# PI2AX.net
KiCad netlist of a schematic drawn in EAGLE
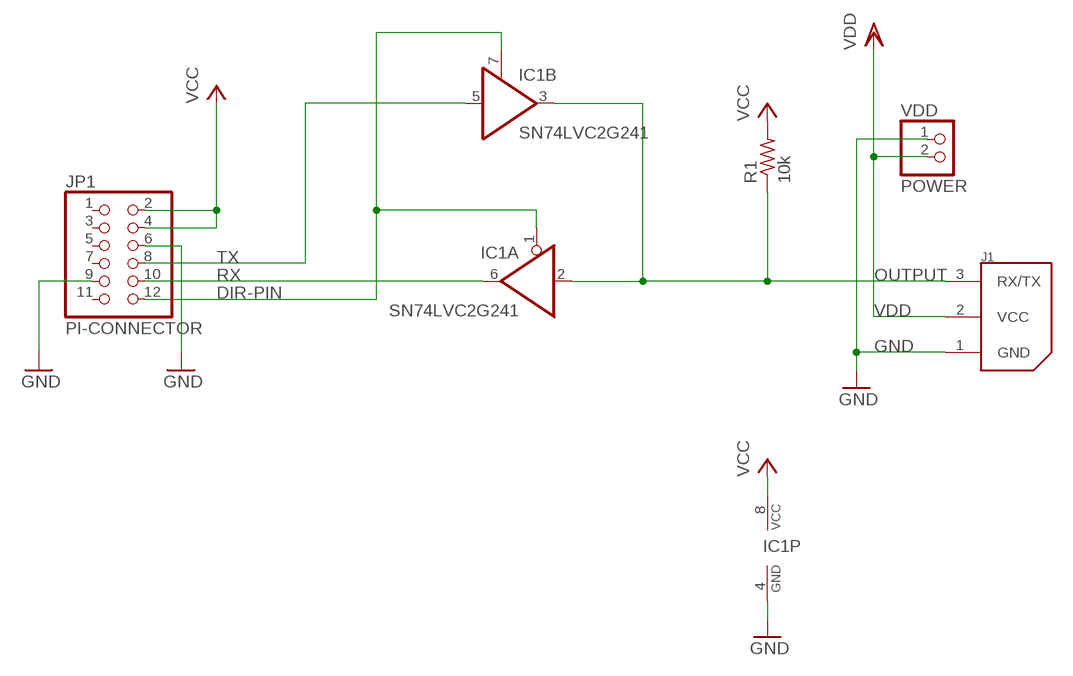
[diagram p0: schematic, sheet 1]

(export (version "E")
  (design (tool "Eeschema 10.0.6"))
  (components
    (comp (ref "IC1")
      (value "SN74LVC2G241")
      (footprint "eagle-import:SSOP08")
      (libsource (lib "eagle-import") (part "SN74LVC2G241"))
    )
    (comp (ref "J1")
      (value "22-03-5035")
      (footprint "eagle-import:5267-3")
      (libsource (lib "eagle-import") (part "22-03-5035"))
    )
    (comp (ref "JP1")
      (value "PI-CONNECTOR")
      (footprint "eagle-import:2X06")
      (libsource (lib "eagle-import") (part "PINHD-2X6"))
    )
    (comp (ref "R1")
      (value "10k")
      (footprint "eagle-import:R0805")
      (libsource (lib "eagle-import") (part "R-US_R0805"))
    )
    (comp (ref "VDD")
      (value "POWER")
      (footprint "eagle-import:1X02")
      (libsource (lib "eagle-import") (part "PINHD-1X2"))
    )
  )
  (nets
    (net (code "1") (name "/DIR-PIN") (class "Default")
      (node (ref "IC1") (pin "1") (pinfunction "OE_1") (pintype "input"))
      (node (ref "IC1") (pin "7") (pinfunction "OE_7") (pintype "input"))
      (node (ref "JP1") (pin "12") (pinfunction "12_12") (pintype "passive"))
    )
    (net (code "2") (name "/OUTPUT") (class "Default")
      (node (ref "IC1") (pin "2") (pinfunction "I_2") (pintype "input"))
      (node (ref "IC1") (pin "3") (pinfunction "O_3") (pintype "output"))
      (node (ref "J1") (pin "3") (pinfunction "RX/TX_3") (pintype "bidirectional"))
      (node (ref "R1") (pin "1") (pinfunction "1_1") (pintype "passive"))
    )
    (net (code "3") (name "/RX") (class "Default")
      (node (ref "IC1") (pin "6") (pinfunction "O_6") (pintype "tri_state"))
      (node (ref "JP1") (pin "10") (pinfunction "10_10") (pintype "passive"))
    )
    (net (code "4") (name "/TX") (class "Default")
      (node (ref "IC1") (pin "5") (pinfunction "I_5") (pintype "input"))
      (node (ref "JP1") (pin "8") (pinfunction "8_8") (pintype "passive"))
    )
    (net (code "5") (name "GND") (class "Default")
      (node (ref "IC1") (pin "4") (pinfunction "GND_4") (pintype "power_in"))
      (node (ref "J1") (pin "1") (pinfunction "GND_1") (pintype "bidirectional"))
      (node (ref "JP1") (pin "6") (pinfunction "6_6") (pintype "passive"))
      (node (ref "JP1") (pin "9") (pinfunction "9_9") (pintype "passive"))
      (node (ref "VDD") (pin "1") (pinfunction "1_1") (pintype "passive"))
    )
    (net (code "6") (name "VCC") (class "Default")
      (node (ref "IC1") (pin "8") (pinfunction "VCC_8") (pintype "power_in"))
      (node (ref "JP1") (pin "2") (pinfunction "2_2") (pintype "passive"))
      (node (ref "JP1") (pin "4") (pinfunction "4_4") (pintype "passive"))
      (node (ref "R1") (pin "2") (pinfunction "2_2") (pintype "passive"))
    )
    (net (code "7") (name "VDD") (class "Default")
      (node (ref "J1") (pin "2") (pinfunction "VCC_2") (pintype "bidirectional"))
      (node (ref "VDD") (pin "2") (pinfunction "2_2") (pintype "passive"))
    )
    (net (code "8") (name "unconnected-(JP1-Pad1)") (class "Default")
      (node (ref "JP1") (pin "1") (pinfunction "1_1") (pintype "passive"))
    )
    (net (code "9") (name "unconnected-(JP1-Pad3)") (class "Default")
      (node (ref "JP1") (pin "3") (pinfunction "3_3") (pintype "passive"))
    )
    (net (code "10") (name "unconnected-(JP1-Pad5)") (class "Default")
      (node (ref "JP1") (pin "5") (pinfunction "5_5") (pintype "passive"))
    )
    (net (code "11") (name "unconnected-(JP1-Pad7)") (class "Default")
      (node (ref "JP1") (pin "7") (pinfunction "7_7") (pintype "passive"))
    )
    (net (code "12") (name "unconnected-(JP1-Pad11)") (class "Default")
      (node (ref "JP1") (pin "11") (pinfunction "11_11") (pintype "passive"))
    )
  )
)
